# octob_pcksBoard.net
KiCad netlist of a schematic drawn in EAGLE
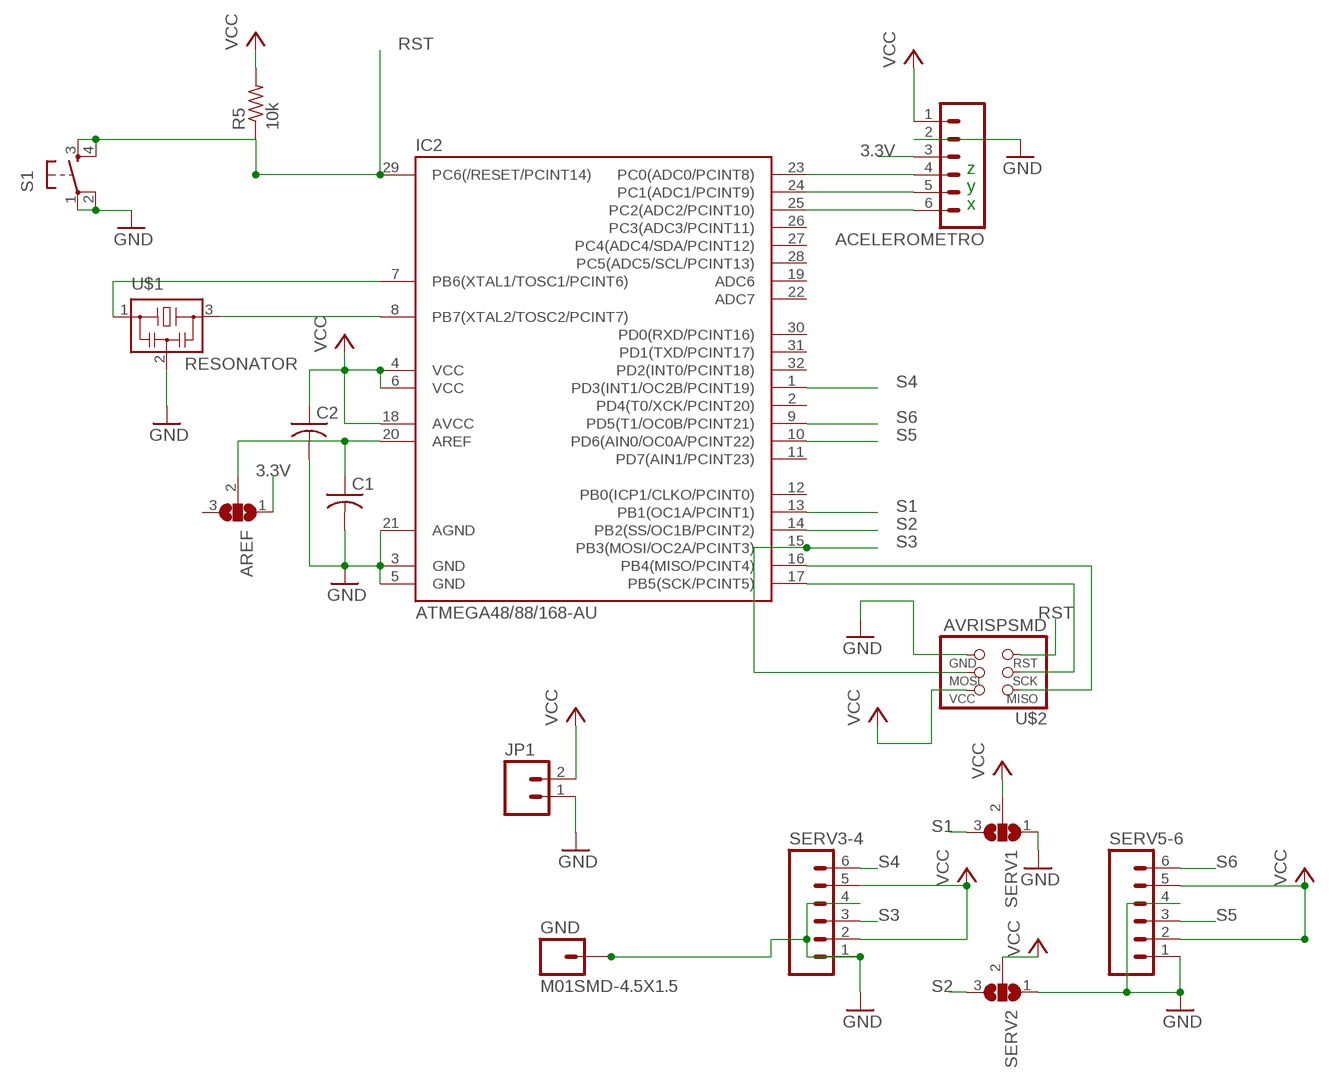
[diagram p0: schematic, sheet 1]

(export (version "E")
  (design (tool "Eeschema 10.0.6"))
  (components
    (comp (ref "ACELEROMETRO")
      (value "M06SMD")
      (footprint "eagle-import:1X06-SMD")
      (libsource (lib "eagle-import") (part "M06SMD"))
    )
    (comp (ref "AREF")
      (value "SJ2WW")
      (footprint "eagle-import:SJ_2W")
      (libsource (lib "eagle-import") (part "SJ2WW"))
    )
    (comp (ref "C1")
      (value "C-USC1206")
      (footprint "eagle-import:C1206")
      (libsource (lib "eagle-import") (part "C-USC1206"))
    )
    (comp (ref "C2")
      (value "C-USC1206")
      (footprint "eagle-import:C1206")
      (libsource (lib "eagle-import") (part "C-USC1206"))
    )
    (comp (ref "GND")
      (value "M01SMD-4.5X1.5")
      (footprint "eagle-import:PAD-1.5X4.5")
      (libsource (lib "eagle-import") (part "M01SMD-4.5X1.5"))
    )
    (comp (ref "IC2")
      (value "ATMEGA48/88/168-AU")
      (footprint "eagle-import:TQFP32-08")
      (libsource (lib "eagle-import") (part "ATMEGA48/88/168-AU"))
    )
    (comp (ref "JP1")
      (value "M02")
      (footprint "eagle-import:1X02_LONGPADS")
      (libsource (lib "eagle-import") (part "M02"))
    )
    (comp (ref "R5")
      (value "10k")
      (footprint "eagle-import:1206")
      (libsource (lib "eagle-import") (part "RESISTOR1206"))
    )
    (comp (ref "S1")
      (value "6MM_SWITCH6MM_SWITCH")
      (footprint "eagle-import:6MM_SWITCH")
      (libsource (lib "eagle-import") (part "6MM_SWITCH6MM_SWITCH"))
    )
    (comp (ref "SERV1")
      (value "SJ2WW")
      (footprint "eagle-import:SJ_2W")
      (libsource (lib "eagle-import") (part "SJ2WW"))
    )
    (comp (ref "SERV2")
      (value "SJ2WW")
      (footprint "eagle-import:SJ_2W")
      (libsource (lib "eagle-import") (part "SJ2WW"))
    )
    (comp (ref "SERV3-4")
      (value "M06SMD")
      (footprint "eagle-import:1X06-SMD")
      (libsource (lib "eagle-import") (part "M06SMD"))
    )
    (comp (ref "SERV5-6")
      (value "M06SMD")
      (footprint "eagle-import:1X06-SMD")
      (libsource (lib "eagle-import") (part "M06SMD"))
    )
    (comp (ref "U$1")
      (value "RESONATOR")
      (footprint "eagle-import:EFOBM")
      (libsource (lib "eagle-import") (part "RESONATOR"))
    )
    (comp (ref "U$2")
      (value "AVRISPSMD")
      (footprint "eagle-import:2X03SMD")
      (libsource (lib "eagle-import") (part "AVRISPSMD"))
    )
  )
  (nets
    (net (code "1") (name "/3.3V") (class "Default")
      (node (ref "ACELEROMETRO") (pin "3") (pinfunction "3_3") (pintype "passive"))
      (node (ref "AREF") (pin "1") (pinfunction "1_1") (pintype "passive"))
    )
    (net (code "2") (name "/RST") (class "Default")
      (node (ref "IC2") (pin "29") (pinfunction "PC6(/RESET/PCINT14)_29") (pintype "bidirectional"))
      (node (ref "R5") (pin "1") (pinfunction "1_1") (pintype "passive"))
      (node (ref "S1") (pin "3") (pinfunction "S_3") (pintype "passive"))
      (node (ref "S1") (pin "4") (pinfunction "S1_4") (pintype "passive"))
      (node (ref "U$2") (pin "5") (pinfunction "RST_5") (pintype "passive"))
    )
    (net (code "3") (name "/S1") (class "Default")
      (node (ref "IC2") (pin "13") (pinfunction "PB1(OC1A/PCINT1)_13") (pintype "bidirectional"))
      (node (ref "SERV1") (pin "3") (pinfunction "3_3") (pintype "passive"))
    )
    (net (code "4") (name "/S2") (class "Default")
      (node (ref "IC2") (pin "14") (pinfunction "PB2(SS/OC1B/PCINT2)_14") (pintype "bidirectional"))
      (node (ref "SERV2") (pin "3") (pinfunction "3_3") (pintype "passive"))
    )
    (net (code "5") (name "/S3") (class "Default")
      (node (ref "IC2") (pin "15") (pinfunction "PB3(MOSI/OC2A/PCINT3)_15") (pintype "bidirectional"))
      (node (ref "SERV3-4") (pin "3") (pinfunction "3_3") (pintype "passive"))
      (node (ref "U$2") (pin "4") (pinfunction "MOSI_4") (pintype "passive"))
    )
    (net (code "6") (name "/S4") (class "Default")
      (node (ref "IC2") (pin "1") (pinfunction "PD3(INT1/OC2B/PCINT19)_1") (pintype "bidirectional"))
      (node (ref "SERV3-4") (pin "6") (pinfunction "6_6") (pintype "passive"))
    )
    (net (code "7") (name "/S5") (class "Default")
      (node (ref "IC2") (pin "10") (pinfunction "PD6(AIN0/OC0A/PCINT22)_10") (pintype "bidirectional"))
      (node (ref "SERV5-6") (pin "3") (pinfunction "3_3") (pintype "passive"))
    )
    (net (code "8") (name "/S6") (class "Default")
      (node (ref "IC2") (pin "9") (pinfunction "PD5(T1/OC0B/PCINT21)_9") (pintype "bidirectional"))
      (node (ref "SERV5-6") (pin "6") (pinfunction "6_6") (pintype "passive"))
    )
    (net (code "9") (name "GND") (class "Default")
      (node (ref "ACELEROMETRO") (pin "2") (pinfunction "2_2") (pintype "passive"))
      (node (ref "C1") (pin "2") (pinfunction "2_2") (pintype "passive"))
      (node (ref "C2") (pin "2") (pinfunction "2_2") (pintype "passive"))
      (node (ref "GND") (pin "P$1") (pinfunction "1_P$1") (pintype "passive"))
      (node (ref "IC2") (pin "21") (pinfunction "AGND_21") (pintype "power_in"))
      (node (ref "IC2") (pin "3") (pinfunction "GND_3") (pintype "power_in"))
      (node (ref "IC2") (pin "5") (pinfunction "GND_5") (pintype "power_in"))
      (node (ref "JP1") (pin "1") (pinfunction "1_1") (pintype "passive"))
      (node (ref "S1") (pin "1") (pinfunction "P_1") (pintype "passive"))
      (node (ref "S1") (pin "2") (pinfunction "P1_2") (pintype "passive"))
      (node (ref "SERV1") (pin "1") (pinfunction "1_1") (pintype "passive"))
      (node (ref "SERV2") (pin "1") (pinfunction "1_1") (pintype "passive"))
      (node (ref "SERV3-4") (pin "1") (pinfunction "1_1") (pintype "passive"))
      (node (ref "SERV3-4") (pin "4") (pinfunction "4_4") (pintype "passive"))
      (node (ref "SERV5-6") (pin "1") (pinfunction "1_1") (pintype "passive"))
      (node (ref "SERV5-6") (pin "4") (pinfunction "4_4") (pintype "passive"))
      (node (ref "U$1") (pin "2") (pinfunction "2_2") (pintype "passive"))
      (node (ref "U$2") (pin "6") (pinfunction "GND_6") (pintype "passive"))
    )
    (net (code "10") (name "Net-(IC2-AREF)") (class "Default")
      (node (ref "AREF") (pin "2") (pinfunction "2_2") (pintype "passive"))
      (node (ref "C1") (pin "1") (pinfunction "1_1") (pintype "passive"))
      (node (ref "IC2") (pin "20") (pinfunction "AREF_20") (pintype "passive"))
    )
    (net (code "11") (name "Net-(IC2-PB4(MISO{slash}PCINT4))") (class "Default")
      (node (ref "IC2") (pin "16") (pinfunction "PB4(MISO/PCINT4)_16") (pintype "bidirectional"))
      (node (ref "U$2") (pin "1") (pinfunction "MISO_1") (pintype "passive"))
    )
    (net (code "12") (name "Net-(IC2-PB5(SCK{slash}PCINT5))") (class "Default")
      (node (ref "IC2") (pin "17") (pinfunction "PB5(SCK/PCINT5)_17") (pintype "bidirectional"))
      (node (ref "U$2") (pin "3") (pinfunction "SCK_3") (pintype "passive"))
    )
    (net (code "13") (name "Net-(IC2-PB6(XTAL1{slash}TOSC1{slash}PCINT6))") (class "Default")
      (node (ref "IC2") (pin "7") (pinfunction "PB6(XTAL1/TOSC1/PCINT6)_7") (pintype "bidirectional"))
      (node (ref "U$1") (pin "1") (pinfunction "1_1") (pintype "passive"))
    )
    (net (code "14") (name "Net-(IC2-PB7(XTAL2{slash}TOSC2{slash}PCINT7))") (class "Default")
      (node (ref "IC2") (pin "8") (pinfunction "PB7(XTAL2/TOSC2/PCINT7)_8") (pintype "bidirectional"))
      (node (ref "U$1") (pin "3") (pinfunction "3_3") (pintype "passive"))
    )
    (net (code "15") (name "Net-(IC2-PC0(ADC0{slash}PCINT8))") (class "Default")
      (node (ref "ACELEROMETRO") (pin "4") (pinfunction "4_4") (pintype "passive"))
      (node (ref "IC2") (pin "23") (pinfunction "PC0(ADC0/PCINT8)_23") (pintype "bidirectional"))
    )
    (net (code "16") (name "Net-(IC2-PC1(ADC1{slash}PCINT9))") (class "Default")
      (node (ref "ACELEROMETRO") (pin "5") (pinfunction "5_5") (pintype "passive"))
      (node (ref "IC2") (pin "24") (pinfunction "PC1(ADC1/PCINT9)_24") (pintype "bidirectional"))
    )
    (net (code "17") (name "Net-(IC2-PC2(ADC2{slash}PCINT10))") (class "Default")
      (node (ref "ACELEROMETRO") (pin "6") (pinfunction "6_6") (pintype "passive"))
      (node (ref "IC2") (pin "25") (pinfunction "PC2(ADC2/PCINT10)_25") (pintype "bidirectional"))
    )
    (net (code "18") (name "VCC") (class "Default")
      (node (ref "ACELEROMETRO") (pin "1") (pinfunction "1_1") (pintype "passive"))
      (node (ref "C2") (pin "1") (pinfunction "1_1") (pintype "passive"))
      (node (ref "IC2") (pin "18") (pinfunction "AVCC_18") (pintype "passive"))
      (node (ref "IC2") (pin "4") (pinfunction "VCC_4") (pintype "power_in"))
      (node (ref "IC2") (pin "6") (pinfunction "VCC_6") (pintype "power_in"))
      (node (ref "JP1") (pin "2") (pinfunction "2_2") (pintype "passive"))
      (node (ref "R5") (pin "2") (pinfunction "2_2") (pintype "passive"))
      (node (ref "SERV1") (pin "2") (pinfunction "2_2") (pintype "passive"))
      (node (ref "SERV2") (pin "2") (pinfunction "2_2") (pintype "passive"))
      (node (ref "SERV3-4") (pin "2") (pinfunction "2_2") (pintype "passive"))
      (node (ref "SERV3-4") (pin "5") (pinfunction "5_5") (pintype "passive"))
      (node (ref "SERV5-6") (pin "2") (pinfunction "2_2") (pintype "passive"))
      (node (ref "SERV5-6") (pin "5") (pinfunction "5_5") (pintype "passive"))
      (node (ref "U$2") (pin "2") (pinfunction "VCC_2") (pintype "passive"))
    )
    (net (code "19") (name "unconnected-(AREF-Pad3)") (class "Default")
      (node (ref "AREF") (pin "3") (pinfunction "3_3") (pintype "passive"))
    )
    (net (code "20") (name "unconnected-(IC2-ADC6-Pad19)") (class "Default")
      (node (ref "IC2") (pin "19") (pinfunction "ADC6_19") (pintype "passive"))
    )
    (net (code "21") (name "unconnected-(IC2-ADC7-Pad22)") (class "Default")
      (node (ref "IC2") (pin "22") (pinfunction "ADC7_22") (pintype "passive"))
    )
    (net (code "22") (name "unconnected-(IC2-PB0(ICP1{slash}CLKO{slash}PCINT0)-Pad12)") (class "Default")
      (node (ref "IC2") (pin "12") (pinfunction "PB0(ICP1/CLKO/PCINT0)_12") (pintype "bidirectional"))
    )
    (net (code "23") (name "unconnected-(IC2-PC3(ADC3{slash}PCINT11)-Pad26)") (class "Default")
      (node (ref "IC2") (pin "26") (pinfunction "PC3(ADC3/PCINT11)_26") (pintype "bidirectional"))
    )
    (net (code "24") (name "unconnected-(IC2-PC4(ADC4{slash}SDA{slash}PCINT12)-Pad27)") (class "Default")
      (node (ref "IC2") (pin "27") (pinfunction "PC4(ADC4/SDA/PCINT12)_27") (pintype "bidirectional"))
    )
    (net (code "25") (name "unconnected-(IC2-PC5(ADC5{slash}SCL{slash}PCINT13)-Pad28)") (class "Default")
      (node (ref "IC2") (pin "28") (pinfunction "PC5(ADC5/SCL/PCINT13)_28") (pintype "bidirectional"))
    )
    (net (code "26") (name "unconnected-(IC2-PD0(RXD{slash}PCINT16)-Pad30)") (class "Default")
      (node (ref "IC2") (pin "30") (pinfunction "PD0(RXD/PCINT16)_30") (pintype "bidirectional"))
    )
    (net (code "27") (name "unconnected-(IC2-PD1(TXD{slash}PCINT17)-Pad31)") (class "Default")
      (node (ref "IC2") (pin "31") (pinfunction "PD1(TXD/PCINT17)_31") (pintype "bidirectional"))
    )
    (net (code "28") (name "unconnected-(IC2-PD2(INT0{slash}PCINT18)-Pad32)") (class "Default")
      (node (ref "IC2") (pin "32") (pinfunction "PD2(INT0/PCINT18)_32") (pintype "bidirectional"))
    )
    (net (code "29") (name "unconnected-(IC2-PD4(T0{slash}XCK{slash}PCINT20)-Pad2)") (class "Default")
      (node (ref "IC2") (pin "2") (pinfunction "PD4(T0/XCK/PCINT20)_2") (pintype "bidirectional"))
    )
    (net (code "30") (name "unconnected-(IC2-PD7(AIN1{slash}PCINT23)-Pad11)") (class "Default")
      (node (ref "IC2") (pin "11") (pinfunction "PD7(AIN1/PCINT23)_11") (pintype "bidirectional"))
    )
  )
)
